# Input_AFE.net
KiCad netlist of a schematic drawn in Altium Designer
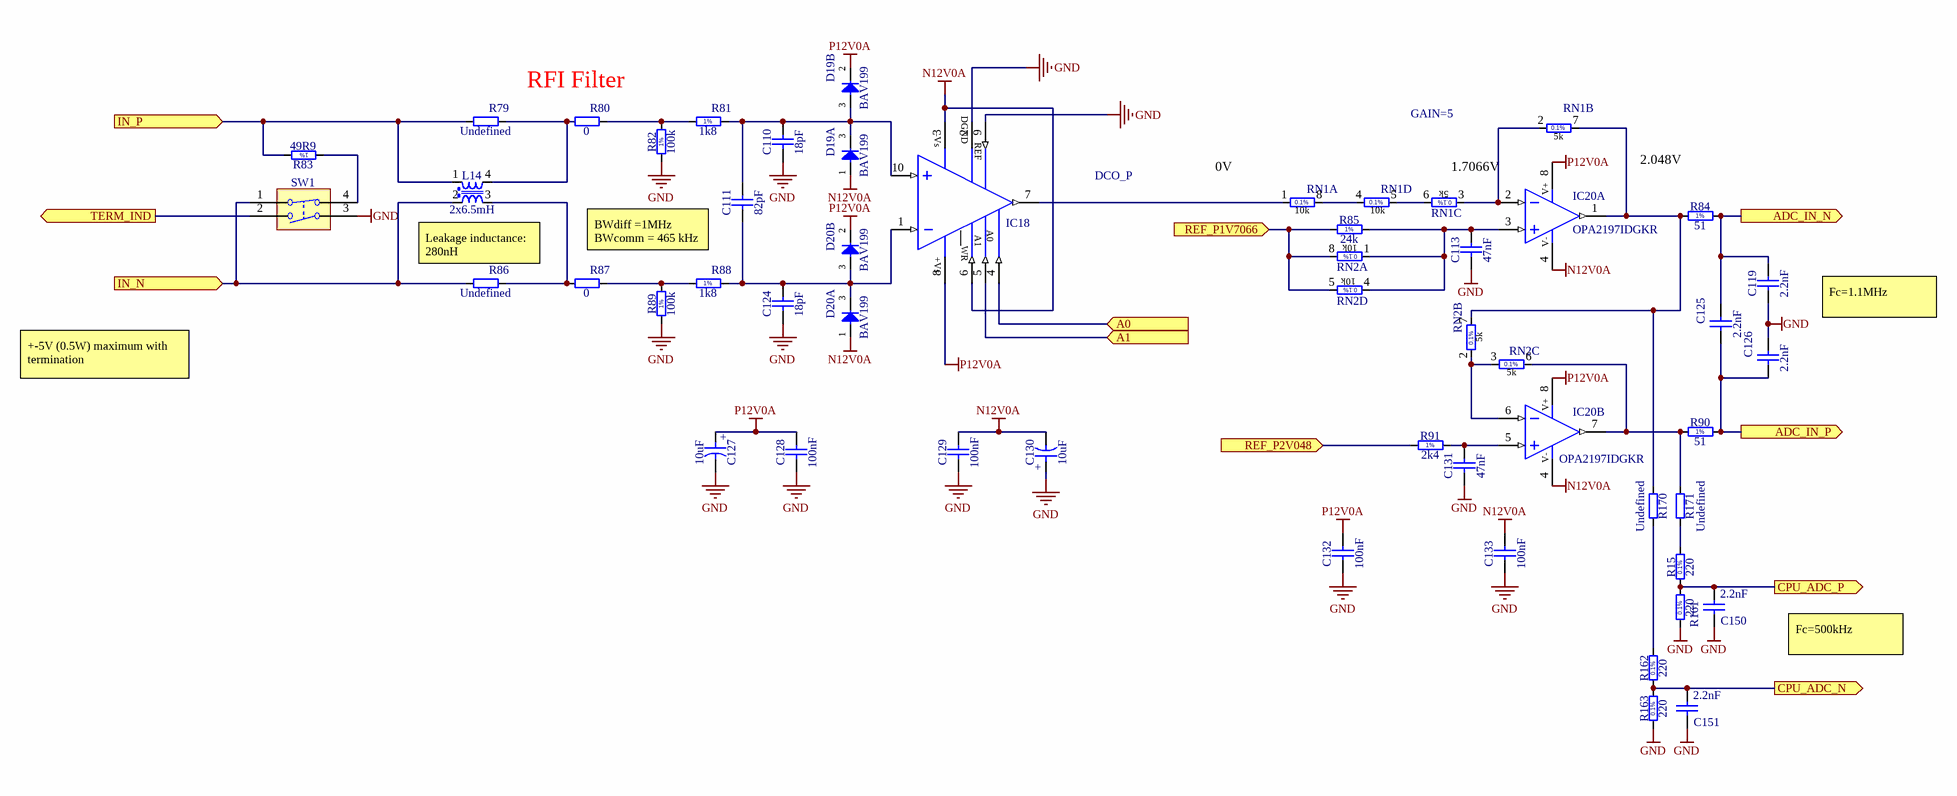
[diagram p0: Input_AFE.SchDoc]

(export (version "E")
  (design (tool "Eeschema 10.0.6"))
  (components
    (comp (ref "C110")
      (value "18pF")
      (footprint "CAPC1608X87N")
      (description "Non-polarised capacitor")
      (fields
        (field (name "PART NUMBER") "CC0603_18PF_50V_5%_NP0")
        (field (name "VOLTAGE") "50V")
        (field (name "AUTHOR") "CERN DEM JLC")
      )
      (libsource (lib "Capacitors") (part "Capacitor - non polarized"))
    )
    (comp (ref "C111")
      (value "82pF")
      (footprint "CAPC2012X90N")
      (description "Non-polarised capacitor")
      (fields
        (field (name "PART NUMBER") "CC0805_82PF_100V_1%_NP0_AVX_08051A820FAT2A")
        (field (name "VOLTAGE") "100V")
        (field (name "AUTHOR") "CERN DEM WB")
      )
      (libsource (lib "Capacitors") (part "Capacitor - non polarized"))
    )
    (comp (ref "C113")
      (value "47nF")
      (footprint "CAPC2012X135N")
      (description "Non-polarised capacitor")
      (fields
        (field (name "PART NUMBER") "CC0805_47NF_25V_5%_C0G")
        (field (name "VOLTAGE") "25V")
        (field (name "AUTHOR") "CERN DEM JLC")
      )
      (libsource (lib "Capacitors") (part "Capacitor - non polarized"))
    )
    (comp (ref "C119")
      (value "2.2nF")
      (footprint "CAPC2013X100N")
      (description "Non-polarised capacitor")
      (fields
        (field (name "PART NUMBER") "CC0805_2.2NF_25V_1%_C0G")
        (field (name "VOLTAGE") "25V")
        (field (name "AUTHOR") "CERN DEM JLC")
      )
      (libsource (lib "Capacitors") (part "Capacitor - non polarized"))
    )
    (comp (ref "C124")
      (value "18pF")
      (footprint "CAPC1608X87N")
      (description "Non-polarised capacitor")
      (fields
        (field (name "PART NUMBER") "CC0603_18PF_50V_5%_NP0")
        (field (name "VOLTAGE") "50V")
        (field (name "AUTHOR") "CERN DEM JLC")
      )
      (libsource (lib "Capacitors") (part "Capacitor - non polarized"))
    )
    (comp (ref "C125")
      (value "2.2nF")
      (footprint "CAPC2013X100N")
      (description "Non-polarised capacitor")
      (fields
        (field (name "PART NUMBER") "CC0805_2.2NF_25V_1%_C0G")
        (field (name "VOLTAGE") "25V")
        (field (name "AUTHOR") "CERN DEM JLC")
      )
      (libsource (lib "Capacitors") (part "Capacitor - non polarized"))
    )
    (comp (ref "C126")
      (value "2.2nF")
      (footprint "CAPC2013X100N")
      (description "Non-polarised capacitor")
      (fields
        (field (name "PART NUMBER") "CC0805_2.2NF_25V_1%_C0G")
        (field (name "VOLTAGE") "25V")
        (field (name "AUTHOR") "CERN DEM JLC")
      )
      (libsource (lib "Capacitors") (part "Capacitor - non polarized"))
    )
    (comp (ref "C127")
      (value "10uF")
      (footprint "CAPMP3216X180N")
      (description "Polarised capacitor")
      (fields
        (field (name "PART NUMBER") "CTE3216-18_10UF_16V_20%_AVX_TCJ")
        (field (name "VOLTAGE") "16V")
        (field (name "AUTHOR") "CERN DEM JLC")
      )
      (libsource (lib "Capacitors") (part "Capacitor - polarized"))
    )
    (comp (ref "C128")
      (value "100nF")
      (footprint "CAPC1005X55N")
      (description "Non-polarised capacitor")
      (fields
        (field (name "PART NUMBER") "CC0402_100NF_16V_10%_X7R")
        (field (name "VOLTAGE") "16V")
        (field (name "AUTHOR") "CERN DEM JLC")
      )
      (libsource (lib "Capacitors") (part "Capacitor - non polarized"))
    )
    (comp (ref "C129")
      (value "100nF")
      (footprint "CAPC1005X55N")
      (description "Non-polarised capacitor")
      (fields
        (field (name "PART NUMBER") "CC0402_100NF_16V_10%_X7R")
        (field (name "VOLTAGE") "16V")
        (field (name "AUTHOR") "CERN DEM JLC")
      )
      (libsource (lib "Capacitors") (part "Capacitor - non polarized"))
    )
    (comp (ref "C130")
      (value "10uF")
      (footprint "CAPMP3216X180N")
      (description "Polarised capacitor")
      (fields
        (field (name "PART NUMBER") "CTE3216-18_10UF_16V_20%_AVX_TCJ")
        (field (name "VOLTAGE") "16V")
        (field (name "AUTHOR") "CERN DEM JLC")
      )
      (libsource (lib "Capacitors") (part "Capacitor - polarized"))
    )
    (comp (ref "C131")
      (value "47nF")
      (footprint "CAPC2012X135N")
      (description "Non-polarised capacitor")
      (fields
        (field (name "PART NUMBER") "CC0805_47NF_25V_5%_C0G")
        (field (name "VOLTAGE") "25V")
        (field (name "AUTHOR") "CERN DEM JLC")
      )
      (libsource (lib "Capacitors") (part "Capacitor - non polarized"))
    )
    (comp (ref "C132")
      (value "100nF")
      (footprint "CAPC1005X55N")
      (description "Non-polarised capacitor")
      (fields
        (field (name "PART NUMBER") "CC0402_100NF_16V_10%_X7R")
        (field (name "VOLTAGE") "16V")
        (field (name "AUTHOR") "CERN DEM JLC")
      )
      (libsource (lib "Capacitors") (part "Capacitor - non polarized"))
    )
    (comp (ref "C133")
      (value "100nF")
      (footprint "CAPC1005X55N")
      (description "Non-polarised capacitor")
      (fields
        (field (name "PART NUMBER") "CC0402_100NF_16V_10%_X7R")
        (field (name "VOLTAGE") "16V")
        (field (name "AUTHOR") "CERN DEM JLC")
      )
      (libsource (lib "Capacitors") (part "Capacitor - non polarized"))
    )
    (comp (ref "C150")
      (value "2.2nF")
      (footprint "CAPC2013X100N")
      (description "Non-polarised capacitor")
      (fields
        (field (name "PART NUMBER") "CC0805_2.2NF_25V_1%_C0G")
        (field (name "VOLTAGE") "25V")
        (field (name "AUTHOR") "CERN DEM JLC")
      )
      (libsource (lib "Capacitors") (part "Capacitor - non polarized"))
    )
    (comp (ref "C151")
      (value "2.2nF")
      (footprint "CAPC2013X100N")
      (description "Non-polarised capacitor")
      (fields
        (field (name "PART NUMBER") "CC0805_2.2NF_25V_1%_C0G")
        (field (name "VOLTAGE") "25V")
        (field (name "AUTHOR") "CERN DEM JLC")
      )
      (libsource (lib "Capacitors") (part "Capacitor - non polarized"))
    )
    (comp (ref "D19")
      (value "BAV199")
      (footprint "SOT95P240X110-3N")
      (description "Serial Diode")
      (fields
        (field (name "VOLTAGE") "75V")
        (field (name "POWER") "250mW")
        (field (name "AUTHOR") "CERN DEM JMW")
      )
      (libsource (lib "ICs And Semiconductors") (part "Diode x2 A1C3_A3C2"))
    )
    (comp (ref "D20")
      (value "BAV199")
      (footprint "SOT95P240X110-3N")
      (description "Serial Diode")
      (fields
        (field (name "VOLTAGE") "75V")
        (field (name "POWER") "250mW")
        (field (name "AUTHOR") "CERN DEM JMW")
      )
      (libsource (lib "ICs And Semiconductors") (part "Diode x2 A1C3_A3C2"))
    )
    (comp (ref "IC18")
      (value "DCO_P")
      (footprint "SOP50P490X110-10N")
      (description "10MHz, 20V/us, G= 1, 2, 5, 10 iCMOS Programmable Gain Instrumentation Amplifier")
      (fields
        (field (name "PART NUMBER") "AD8250ARMZ")
        (field (name "MANUFACTURER") "ANALOG DEVICES")
        (field (name "AUTHOR") "CERN DEM JLC")
      )
      (libsource (lib "ICs And Semiconductors") (part "AD8250"))
    )
    (comp (ref "IC20")
      (value "OPA2197IDGKR")
      (footprint "SOP65P490X110-8N")
      (description "36-V, Precision, Rail-to-Rail Input Output, Low Offset Voltage Op Amp 8-VSSOP")
      (fields (field (name "MANUFACTURER") "TEXAS INSTRUMENTS") (field (name "AUTHOR") "GK"))
      (libsource (lib "LIBRARY_SCH") (part "OA_OPA2197IDGKR"))
    )
    (comp (ref "L14")
      (value "2x6.5mH")
      (footprint "IND_WURTH_WE-SL2")
      (description "Inductor Common Mode")
      (fields
        (field (name "PART NUMBER") "IND_6.5MH_50%_WURTH_WE-SL2-744229")
        (field (name "POWER") "400mA")
        (field (name "AUTHOR") "CERN DEM JLC")
      )
      (libsource (lib "Inductors & Transformers") (part "Inductor Common Mode 1Dot-4 2Dot-3"))
    )
    (comp (ref "R15")
      (value "220")
      (footprint "RESC1608X64N")
      (description "Resistor - 0.1%")
      (fields
        (field (name "PART NUMBER") "R0603_220R_0.1%_0.1W_25PPM")
        (field (name "POWER") "0.1W")
        (field (name "AUTHOR") "CERN DEM JLC")
      )
      (libsource (lib "Resistors") (part "Resistor - 0.1%"))
    )
    (comp (ref "R79")
      (value "Undefined")
      (footprint "RESC1608X55N")
      (description "Resistor")
      (fields (field (name "PART NUMBER") "R0603_NO-VALUE") (field (name "AUTHOR") "CERN DEM JLC"))
      (libsource (lib "Resistors") (part "Resistor"))
    )
    (comp (ref "R80")
      (value "0")
      (footprint "RESC1608X55N")
      (description "Resistor")
      (fields
        (field (name "PART NUMBER") "R0603_0R_JUMPER")
        (field (name "MANUFACTURER") "GENERIC")
        (field (name "AUTHOR") "CERN DEM JLC")
      )
      (libsource (lib "Resistors") (part "Resistor"))
    )
    (comp (ref "R81")
      (value "1k8")
      (footprint "RESC1608X55N")
      (description "Resistor - 1%")
      (fields
        (field (name "PART NUMBER") "R0603_1K8_1%_0.1W_100PPM")
        (field (name "POWER") "0.1W")
        (field (name "AUTHOR") "CERN DEM JLC")
      )
      (libsource (lib "Resistors") (part "Resistor - 1%"))
    )
    (comp (ref "R82")
      (value "100k")
      (footprint "RESC1608X55N")
      (description "Resistor - 1%")
      (fields
        (field (name "PART NUMBER") "R0603_100K_1%_0.1W_100PPM")
        (field (name "POWER") "0.1W")
        (field (name "AUTHOR") "CERN DEM JLC")
      )
      (libsource (lib "Resistors") (part "Resistor - 1%"))
    )
    (comp (ref "R83")
      (value "49R9")
      (footprint "RESC6331X70N")
      (description "Resistor - 1%")
      (fields
        (field (name "PART NUMBER") "R2512_49R9_1%_1W_100PPM_VISHAY_CRCW")
        (field (name "POWER") "1W")
        (field (name "AUTHOR") "CERN DEM JLC")
      )
      (libsource (lib "Resistors") (part "Resistor - 1%"))
    )
    (comp (ref "R84")
      (value "51")
      (footprint "RESC1005X40N")
      (description "Resistor - 1%")
      (fields
        (field (name "PART NUMBER") "R0402_51R_1%_0.0625W_100PPM")
        (field (name "POWER") "0.0625W")
        (field (name "AUTHOR") "CERN DEM JLC")
      )
      (libsource (lib "Resistors") (part "Resistor - 1%"))
    )
    (comp (ref "R85")
      (value "24k")
      (footprint "RESC1608X55N")
      (description "Resistor - 1%")
      (fields
        (field (name "PART NUMBER") "R0603_24K_1%_0.1W_100PPM")
        (field (name "POWER") "0.1W")
        (field (name "AUTHOR") "CERN DEM JLC")
      )
      (libsource (lib "Resistors") (part "Resistor - 1%"))
    )
    (comp (ref "R86")
      (value "Undefined")
      (footprint "RESC1608X55N")
      (description "Resistor")
      (fields (field (name "PART NUMBER") "R0603_NO-VALUE") (field (name "AUTHOR") "CERN DEM JLC"))
      (libsource (lib "Resistors") (part "Resistor"))
    )
    (comp (ref "R87")
      (value "0")
      (footprint "RESC1608X55N")
      (description "Resistor")
      (fields
        (field (name "PART NUMBER") "R0603_0R_JUMPER")
        (field (name "MANUFACTURER") "GENERIC")
        (field (name "AUTHOR") "CERN DEM JLC")
      )
      (libsource (lib "Resistors") (part "Resistor"))
    )
    (comp (ref "R88")
      (value "1k8")
      (footprint "RESC1608X55N")
      (description "Resistor - 1%")
      (fields
        (field (name "PART NUMBER") "R0603_1K8_1%_0.1W_100PPM")
        (field (name "POWER") "0.1W")
        (field (name "AUTHOR") "CERN DEM JLC")
      )
      (libsource (lib "Resistors") (part "Resistor - 1%"))
    )
    (comp (ref "R89")
      (value "100k")
      (footprint "RESC1608X55N")
      (description "Resistor - 1%")
      (fields
        (field (name "PART NUMBER") "R0603_100K_1%_0.1W_100PPM")
        (field (name "POWER") "0.1W")
        (field (name "AUTHOR") "CERN DEM JLC")
      )
      (libsource (lib "Resistors") (part "Resistor - 1%"))
    )
    (comp (ref "R90")
      (value "51")
      (footprint "RESC1005X40N")
      (description "Resistor - 1%")
      (fields
        (field (name "PART NUMBER") "R0402_51R_1%_0.0625W_100PPM")
        (field (name "POWER") "0.0625W")
        (field (name "AUTHOR") "CERN DEM JLC")
      )
      (libsource (lib "Resistors") (part "Resistor - 1%"))
    )
    (comp (ref "R91")
      (value "2k4")
      (footprint "RESC1005X40N")
      (description "Resistor - 1%")
      (fields
        (field (name "PART NUMBER") "R0402_2K4_1%_0.0625W_100PPM")
        (field (name "POWER") "0.0625W")
        (field (name "AUTHOR") "CERN DEM JLC")
      )
      (libsource (lib "Resistors") (part "Resistor - 1%"))
    )
    (comp (ref "R161")
      (value "220")
      (footprint "RESC1608X64N")
      (description "Resistor - 0.1%")
      (fields
        (field (name "PART NUMBER") "R0603_220R_0.1%_0.1W_25PPM")
        (field (name "POWER") "0.1W")
        (field (name "AUTHOR") "CERN DEM JLC")
      )
      (libsource (lib "Resistors") (part "Resistor - 0.1%"))
    )
    (comp (ref "R162")
      (value "220")
      (footprint "RESC1608X64N")
      (description "Resistor - 0.1%")
      (fields
        (field (name "PART NUMBER") "R0603_220R_0.1%_0.1W_25PPM")
        (field (name "POWER") "0.1W")
        (field (name "AUTHOR") "CERN DEM JLC")
      )
      (libsource (lib "Resistors") (part "Resistor - 0.1%"))
    )
    (comp (ref "R163")
      (value "220")
      (footprint "RESC1608X64N")
      (description "Resistor - 0.1%")
      (fields
        (field (name "PART NUMBER") "R0603_220R_0.1%_0.1W_25PPM")
        (field (name "POWER") "0.1W")
        (field (name "AUTHOR") "CERN DEM JLC")
      )
      (libsource (lib "Resistors") (part "Resistor - 0.1%"))
    )
    (comp (ref "R170")
      (value "Undefined")
      (footprint "RESC1608X55N")
      (description "Resistor")
      (fields (field (name "PART NUMBER") "R0603_NO-VALUE") (field (name "AUTHOR") "CERN DEM JLC"))
      (libsource (lib "Resistors") (part "Resistor"))
    )
    (comp (ref "R171")
      (value "Undefined")
      (footprint "RESC1608X55N")
      (description "Resistor")
      (fields (field (name "PART NUMBER") "R0603_NO-VALUE") (field (name "AUTHOR") "CERN DEM JLC"))
      (libsource (lib "Resistors") (part "Resistor"))
    )
    (comp (ref "RN1")
      (value "10k 5K 5K 10K")
      (footprint "SOIC127P600X175-8N")
      (description "DIL8 Resistor Network 4 Resistors 10k-5k-5k-10k 0.1%")
      (fields
        (field (name "PART NUMBER") "RN_10K_5K_VISHAY_AORN2-1AT3")
        (field (name "POWER") "4x0.1W")
        (field (name "AUTHOR") "CERN DEM JLC")
      )
      (libsource (lib "Resistors") (part "RN DIL8_4xR_10k-5k-5k-10k_0.1%"))
    )
    (comp (ref "RN2")
      (value "10k 5K 5K 10K")
      (footprint "SOIC127P600X175-8N")
      (description "DIL8 Resistor Network 4 Resistors 10k-5k-5k-10k 0.1%")
      (fields
        (field (name "PART NUMBER") "RN_10K_5K_VISHAY_AORN2-1AT3")
        (field (name "POWER") "4x0.1W")
        (field (name "AUTHOR") "CERN DEM JLC")
      )
      (libsource (lib "Resistors") (part "RN DIL8_4xR_10k-5k-5k-10k_0.1%"))
    )
    (comp (ref "SW1")
      (value "Switch")
      (footprint "SW_CTS_204-121ST")
      (description "2x SPST DIP Switch 1NO + 1NF")
      (fields
        (field (name "PART NUMBER") "SW_CTS_204-121ST")
        (field (name "MANUFACTURER") "CTS")
        (field (name "AUTHOR") "CERN DEM JLC")
      )
      (libsource (lib "Eletro-mechanical") (part "SW_CTS_204-121ST"))
    )
  )
  (nets
    (net (code "1") (name "/A0") (class "Default")
      (node (ref "IC18") (pin "4") (pinfunction "A0_4") (pintype "input"))
    )
    (net (code "2") (name "/A1") (class "Default")
      (node (ref "IC18") (pin "5") (pinfunction "A1_5") (pintype "input"))
    )
    (net (code "3") (name "/ADC_IN_N") (class "Default")
      (node (ref "C119") (pin "2") (pinfunction "2_2") (pintype "passive"))
      (node (ref "C125") (pin "2") (pinfunction "2_2") (pintype "passive"))
      (node (ref "R84") (pin "2") (pinfunction "2_2") (pintype "passive"))
    )
    (net (code "4") (name "/ADC_IN_P") (class "Default")
      (node (ref "C125") (pin "1") (pinfunction "1_1") (pintype "passive"))
      (node (ref "C126") (pin "1") (pinfunction "1_1") (pintype "passive"))
      (node (ref "R90") (pin "2") (pinfunction "2_2") (pintype "passive"))
    )
    (net (code "5") (name "/CPU_ADC_N") (class "Default")
      (node (ref "C151") (pin "2") (pinfunction "2_2") (pintype "passive"))
      (node (ref "R162") (pin "1") (pinfunction "1_1") (pintype "passive"))
      (node (ref "R163") (pin "2") (pinfunction "2_2") (pintype "passive"))
    )
    (net (code "6") (name "/CPU_ADC_P") (class "Default")
      (node (ref "C150") (pin "2") (pinfunction "2_2") (pintype "passive"))
      (node (ref "R15") (pin "1") (pinfunction "1_1") (pintype "passive"))
      (node (ref "R161") (pin "2") (pinfunction "2_2") (pintype "passive"))
    )
    (net (code "7") (name "/IN_N") (class "Default")
      (node (ref "L14") (pin "2") (pinfunction "2_2") (pintype "passive"))
      (node (ref "R86") (pin "1") (pinfunction "1_1") (pintype "passive"))
      (node (ref "SW1") (pin "1") (pinfunction "1_1") (pintype "passive"))
    )
    (net (code "8") (name "/IN_P") (class "Default")
      (node (ref "L14") (pin "1") (pinfunction "1_1") (pintype "passive"))
      (node (ref "R79") (pin "1") (pinfunction "1_1") (pintype "passive"))
      (node (ref "R83") (pin "2") (pinfunction "2_2") (pintype "passive"))
    )
    (net (code "9") (name "/REF_P1V7066") (class "Default")
      (node (ref "R85") (pin "1") (pinfunction "1_1") (pintype "passive"))
      (node (ref "RN2") (pin "5") (pinfunction "5_5") (pintype "passive"))
      (node (ref "RN2") (pin "8") (pinfunction "8_8") (pintype "passive"))
    )
    (net (code "10") (name "/REF_P2V048") (class "Default")
      (node (ref "R91") (pin "1") (pinfunction "1_1") (pintype "passive"))
    )
    (net (code "11") (name "/TERM_IND") (class "Default")
      (node (ref "SW1") (pin "2") (pinfunction "2_2") (pintype "passive"))
    )
    (net (code "12") (name "GND") (class "Default")
      (node (ref "C110") (pin "1") (pinfunction "1_1") (pintype "passive"))
      (node (ref "C113") (pin "1") (pinfunction "1_1") (pintype "passive"))
      (node (ref "C119") (pin "1") (pinfunction "1_1") (pintype "passive"))
      (node (ref "C124") (pin "1") (pinfunction "1_1") (pintype "passive"))
      (node (ref "C126") (pin "2") (pinfunction "2_2") (pintype "passive"))
      (node (ref "C127") (pin "2") (pinfunction "2_2") (pintype "passive"))
      (node (ref "C128") (pin "1") (pinfunction "1_1") (pintype "passive"))
      (node (ref "C129") (pin "1") (pinfunction "1_1") (pintype "passive"))
      (node (ref "C130") (pin "1") (pinfunction "1_1") (pintype "passive"))
      (node (ref "C131") (pin "1") (pinfunction "1_1") (pintype "passive"))
      (node (ref "C132") (pin "1") (pinfunction "1_1") (pintype "passive"))
      (node (ref "C133") (pin "1") (pinfunction "1_1") (pintype "passive"))
      (node (ref "C150") (pin "1") (pinfunction "1_1") (pintype "passive"))
      (node (ref "C151") (pin "1") (pinfunction "1_1") (pintype "passive"))
      (node (ref "IC18") (pin "2") (pinfunction "DGND_2") (pintype "power_in"))
      (node (ref "IC18") (pin "9") (pinfunction "REF_9") (pintype "input"))
      (node (ref "R161") (pin "1") (pinfunction "1_1") (pintype "passive"))
      (node (ref "R163") (pin "1") (pinfunction "1_1") (pintype "passive"))
      (node (ref "R82") (pin "1") (pinfunction "1_1") (pintype "passive"))
      (node (ref "R89") (pin "1") (pinfunction "1_1") (pintype "passive"))
      (node (ref "SW1") (pin "3") (pinfunction "3_3") (pintype "passive"))
    )
    (net (code "13") (name "N12V0A") (class "Default")
      (node (ref "C129") (pin "2") (pinfunction "2_2") (pintype "passive"))
      (node (ref "C130") (pin "2") (pinfunction "2_2") (pintype "passive"))
      (node (ref "C133") (pin "2") (pinfunction "2_2") (pintype "passive"))
      (node (ref "D19") (pin "1") (pinfunction "A_1") (pintype "passive"))
      (node (ref "D20") (pin "1") (pinfunction "A_1") (pintype "passive"))
      (node (ref "IC18") (pin "3") (pinfunction "-VS_3") (pintype "power_in"))
      (node (ref "IC18") (pin "6") (pinfunction "~{WR}_6") (pintype "input"))
      (node (ref "IC20") (pin "4") (pinfunction "V-_4") (pintype "power_in"))
    )
    (net (code "14") (name "Net-(D19A-COMAC)") (class "Default")
      (node (ref "C110") (pin "2") (pinfunction "2_2") (pintype "passive"))
      (node (ref "C111") (pin "2") (pinfunction "2_2") (pintype "passive"))
      (node (ref "D19") (pin "3") (pinfunction "COMAC_3") (pintype "passive"))
      (node (ref "IC18") (pin "10") (pinfunction "+IN_10") (pintype "input"))
      (node (ref "R81") (pin "2") (pinfunction "2_2") (pintype "passive"))
    )
    (net (code "15") (name "Net-(D20A-COMAC)") (class "Default")
      (node (ref "C111") (pin "1") (pinfunction "1_1") (pintype "passive"))
      (node (ref "C124") (pin "2") (pinfunction "2_2") (pintype "passive"))
      (node (ref "D20") (pin "3") (pinfunction "COMAC_3") (pintype "passive"))
      (node (ref "IC18") (pin "1") (pinfunction "-IN_1") (pintype "input"))
      (node (ref "R88") (pin "2") (pinfunction "2_2") (pintype "passive"))
    )
    (net (code "16") (name "Net-(IC18-OUT)") (class "Default")
      (node (ref "IC18") (pin "7") (pinfunction "OUT_7") (pintype "output"))
      (node (ref "RN1") (pin "1") (pinfunction "1_1") (pintype "passive"))
    )
    (net (code "17") (name "Net-(IC20A-IN+)") (class "Default")
      (node (ref "C113") (pin "2") (pinfunction "2_2") (pintype "passive"))
      (node (ref "IC20") (pin "3") (pinfunction "IN+_3") (pintype "input"))
      (node (ref "R85") (pin "2") (pinfunction "2_2") (pintype "passive"))
      (node (ref "RN2") (pin "1") (pinfunction "1_1") (pintype "passive"))
      (node (ref "RN2") (pin "4") (pinfunction "4_4") (pintype "passive"))
    )
    (net (code "18") (name "Net-(IC20A-IN-)") (class "Default")
      (node (ref "IC20") (pin "2") (pinfunction "IN-_2") (pintype "input"))
      (node (ref "RN1") (pin "2") (pinfunction "2_2") (pintype "passive"))
      (node (ref "RN1") (pin "3") (pinfunction "3_3") (pintype "passive"))
    )
    (net (code "19") (name "Net-(IC20A-OUT)") (class "Default")
      (node (ref "IC20") (pin "1") (pinfunction "OUT_1") (pintype "output"))
      (node (ref "R170") (pin "1") (pinfunction "1_1") (pintype "passive"))
      (node (ref "R84") (pin "1") (pinfunction "1_1") (pintype "passive"))
      (node (ref "RN1") (pin "7") (pinfunction "7_7") (pintype "passive"))
      (node (ref "RN2") (pin "7") (pinfunction "7_7") (pintype "passive"))
    )
    (net (code "20") (name "Net-(IC20B-IN+)") (class "Default")
      (node (ref "C131") (pin "2") (pinfunction "2_2") (pintype "passive"))
      (node (ref "IC20") (pin "5") (pinfunction "IN+_5") (pintype "input"))
      (node (ref "R91") (pin "2") (pinfunction "2_2") (pintype "passive"))
    )
    (net (code "21") (name "Net-(IC20B-IN-)") (class "Default")
      (node (ref "IC20") (pin "6") (pinfunction "IN-_6") (pintype "input"))
      (node (ref "RN2") (pin "2") (pinfunction "2_2") (pintype "passive"))
      (node (ref "RN2") (pin "3") (pinfunction "3_3") (pintype "passive"))
    )
    (net (code "22") (name "Net-(IC20B-OUT)") (class "Default")
      (node (ref "IC20") (pin "7") (pinfunction "OUT_7") (pintype "output"))
      (node (ref "R171") (pin "1") (pinfunction "1_1") (pintype "passive"))
      (node (ref "R90") (pin "1") (pinfunction "1_1") (pintype "passive"))
      (node (ref "RN2") (pin "6") (pinfunction "6_6") (pintype "passive"))
    )
    (net (code "23") (name "Net-(L14-Pad3)") (class "Default")
      (node (ref "L14") (pin "3") (pinfunction "3_3") (pintype "passive"))
      (node (ref "R86") (pin "2") (pinfunction "2_2") (pintype "passive"))
      (node (ref "R87") (pin "1") (pinfunction "1_1") (pintype "passive"))
    )
    (net (code "24") (name "Net-(L14-Pad4)") (class "Default")
      (node (ref "L14") (pin "4") (pinfunction "4_4") (pintype "passive"))
      (node (ref "R79") (pin "2") (pinfunction "2_2") (pintype "passive"))
      (node (ref "R80") (pin "1") (pinfunction "1_1") (pintype "passive"))
    )
    (net (code "25") (name "Net-(R15-Pad2)") (class "Default")
      (node (ref "R15") (pin "2") (pinfunction "2_2") (pintype "passive"))
      (node (ref "R171") (pin "2") (pinfunction "2_2") (pintype "passive"))
    )
    (net (code "26") (name "Net-(R80-Pad2)") (class "Default")
      (node (ref "R80") (pin "2") (pinfunction "2_2") (pintype "passive"))
      (node (ref "R81") (pin "1") (pinfunction "1_1") (pintype "passive"))
      (node (ref "R82") (pin "2") (pinfunction "2_2") (pintype "passive"))
    )
    (net (code "27") (name "Net-(R83-Pad1)") (class "Default")
      (node (ref "R83") (pin "1") (pinfunction "1_1") (pintype "passive"))
      (node (ref "SW1") (pin "4") (pinfunction "4_4") (pintype "passive"))
    )
    (net (code "28") (name "Net-(R87-Pad2)") (class "Default")
      (node (ref "R87") (pin "2") (pinfunction "2_2") (pintype "passive"))
      (node (ref "R88") (pin "1") (pinfunction "1_1") (pintype "passive"))
      (node (ref "R89") (pin "2") (pinfunction "2_2") (pintype "passive"))
    )
    (net (code "29") (name "Net-(R162-Pad2)") (class "Default")
      (node (ref "R162") (pin "2") (pinfunction "2_2") (pintype "passive"))
      (node (ref "R170") (pin "2") (pinfunction "2_2") (pintype "passive"))
    )
    (net (code "30") (name "Net-(RN1-Pad4)") (class "Default")
      (node (ref "RN1") (pin "4") (pinfunction "4_4") (pintype "passive"))
      (node (ref "RN1") (pin "8") (pinfunction "8_8") (pintype "passive"))
    )
    (net (code "31") (name "Net-(RN1-Pad5)") (class "Default")
      (node (ref "RN1") (pin "5") (pinfunction "5_5") (pintype "passive"))
      (node (ref "RN1") (pin "6") (pinfunction "6_6") (pintype "passive"))
    )
    (net (code "32") (name "P12V0A") (class "Default")
      (node (ref "C127") (pin "1") (pinfunction "1_1") (pintype "passive"))
      (node (ref "C128") (pin "2") (pinfunction "2_2") (pintype "passive"))
      (node (ref "C132") (pin "2") (pinfunction "2_2") (pintype "passive"))
      (node (ref "D19") (pin "2") (pinfunction "C_2") (pintype "passive"))
      (node (ref "D20") (pin "2") (pinfunction "C_2") (pintype "passive"))
      (node (ref "IC18") (pin "8") (pinfunction "+VS_8") (pintype "power_in"))
      (node (ref "IC20") (pin "8") (pinfunction "V+_8") (pintype "power_in"))
    )
  )
)
